# NEW_LINE.net
KiCad netlist of a schematic drawn in EAGLE
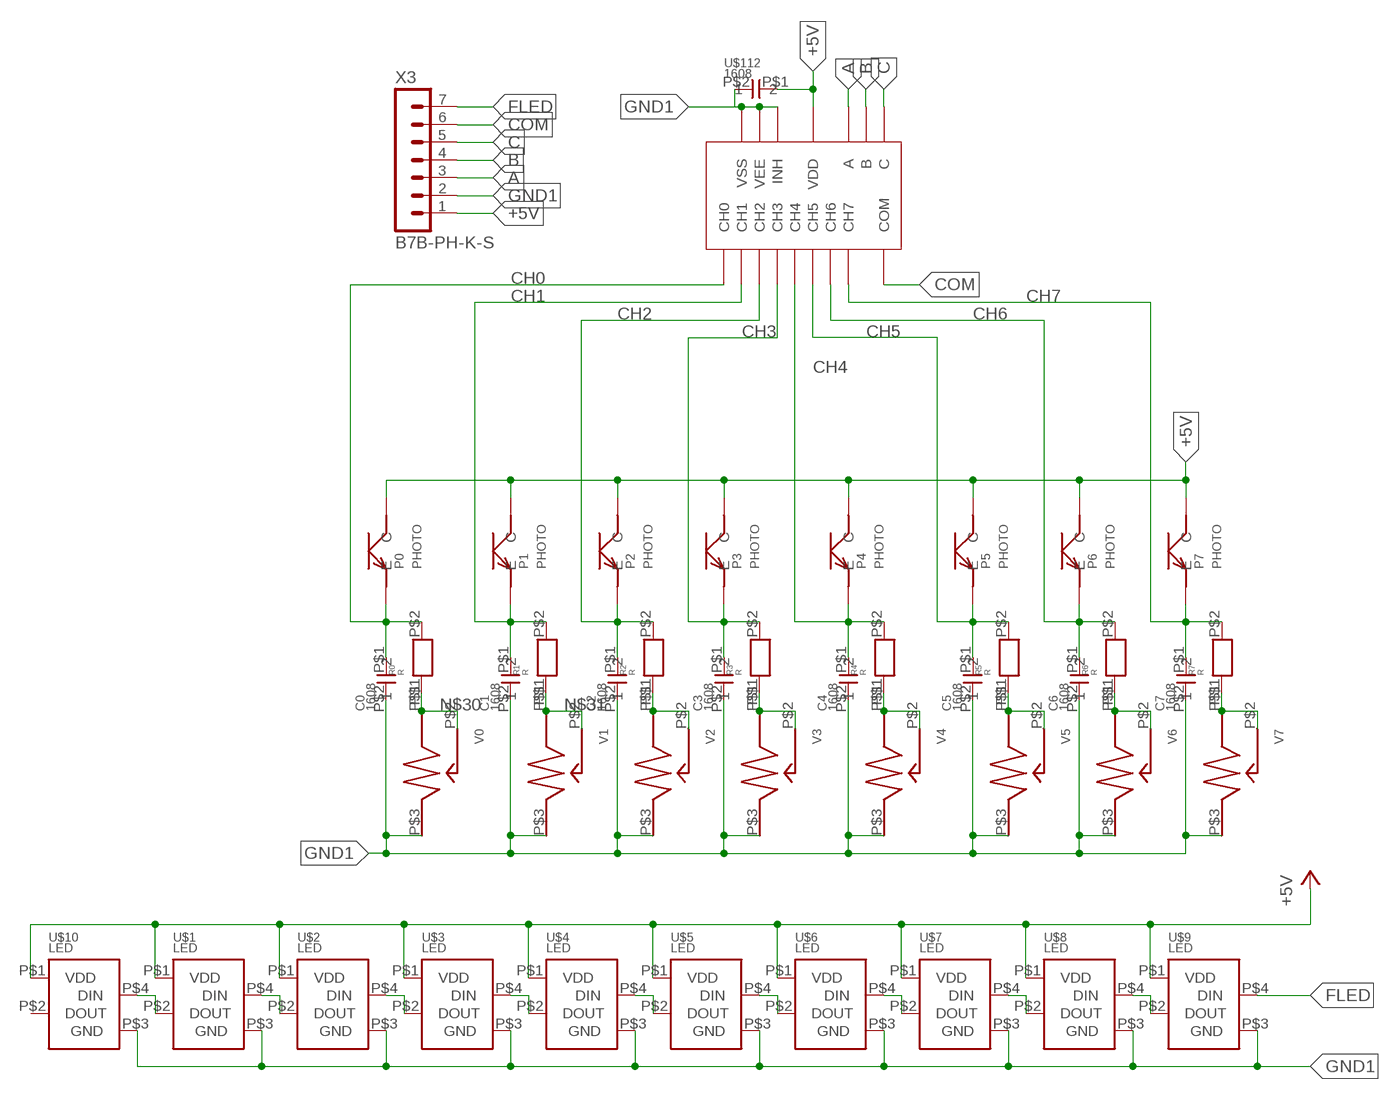
[diagram p0: schematic, sheet 2]

(export (version "E")
  (design (tool "Eeschema 10.0.6"))
  (components
    (comp (ref "C0")
      (value "1608")
      (footprint "eagle-import:CON")
      (libsource (lib "eagle-import") (part "1608"))
    )
    (comp (ref "C1")
      (value "1608")
      (footprint "eagle-import:CON")
      (libsource (lib "eagle-import") (part "1608"))
    )
    (comp (ref "C2")
      (value "1608")
      (footprint "eagle-import:CON")
      (libsource (lib "eagle-import") (part "1608"))
    )
    (comp (ref "C3")
      (value "1608")
      (footprint "eagle-import:CON")
      (libsource (lib "eagle-import") (part "1608"))
    )
    (comp (ref "C4")
      (value "1608")
      (footprint "eagle-import:CON")
      (libsource (lib "eagle-import") (part "1608"))
    )
    (comp (ref "C5")
      (value "1608")
      (footprint "eagle-import:CON")
      (libsource (lib "eagle-import") (part "1608"))
    )
    (comp (ref "C6")
      (value "1608")
      (footprint "eagle-import:CON")
      (libsource (lib "eagle-import") (part "1608"))
    )
    (comp (ref "C7")
      (value "1608")
      (footprint "eagle-import:CON")
      (libsource (lib "eagle-import") (part "1608"))
    )
    (comp (ref "P0")
      (value "PHOTO")
      (footprint "eagle-import:PHOTO")
      (libsource (lib "eagle-import") (part "PHOTO"))
    )
    (comp (ref "P1")
      (value "PHOTO")
      (footprint "eagle-import:PHOTO")
      (libsource (lib "eagle-import") (part "PHOTO"))
    )
    (comp (ref "P2")
      (value "PHOTO")
      (footprint "eagle-import:PHOTO")
      (libsource (lib "eagle-import") (part "PHOTO"))
    )
    (comp (ref "P3")
      (value "PHOTO")
      (footprint "eagle-import:PHOTO")
      (libsource (lib "eagle-import") (part "PHOTO"))
    )
    (comp (ref "P4")
      (value "PHOTO")
      (footprint "eagle-import:PHOTO")
      (libsource (lib "eagle-import") (part "PHOTO"))
    )
    (comp (ref "P5")
      (value "PHOTO")
      (footprint "eagle-import:PHOTO")
      (libsource (lib "eagle-import") (part "PHOTO"))
    )
    (comp (ref "P6")
      (value "PHOTO")
      (footprint "eagle-import:PHOTO")
      (libsource (lib "eagle-import") (part "PHOTO"))
    )
    (comp (ref "P7")
      (value "PHOTO")
      (footprint "eagle-import:PHOTO")
      (libsource (lib "eagle-import") (part "PHOTO"))
    )
    (comp (ref "R0") (value "R") (footprint "eagle-import:1608") (libsource (lib "eagle-import") (part "R")))
    (comp (ref "R1") (value "R") (footprint "eagle-import:1608") (libsource (lib "eagle-import") (part "R")))
    (comp (ref "R2") (value "R") (footprint "eagle-import:1608") (libsource (lib "eagle-import") (part "R")))
    (comp (ref "R3") (value "R") (footprint "eagle-import:1608") (libsource (lib "eagle-import") (part "R")))
    (comp (ref "R4") (value "R") (footprint "eagle-import:1608") (libsource (lib "eagle-import") (part "R")))
    (comp (ref "R5") (value "R") (footprint "eagle-import:1608") (libsource (lib "eagle-import") (part "R")))
    (comp (ref "R6") (value "R") (footprint "eagle-import:1608") (libsource (lib "eagle-import") (part "R")))
    (comp (ref "R7") (value "R") (footprint "eagle-import:1608") (libsource (lib "eagle-import") (part "R")))
    (comp (ref "U$1")
      (value "LED")
      (footprint "eagle-import:LED")
      (libsource (lib "eagle-import") (part "LED"))
    )
    (comp (ref "U$2")
      (value "LED")
      (footprint "eagle-import:LED")
      (libsource (lib "eagle-import") (part "LED"))
    )
    (comp (ref "U$3")
      (value "LED")
      (footprint "eagle-import:LED")
      (libsource (lib "eagle-import") (part "LED"))
    )
    (comp (ref "U$4")
      (value "LED")
      (footprint "eagle-import:LED")
      (libsource (lib "eagle-import") (part "LED"))
    )
    (comp (ref "U$5")
      (value "LED")
      (footprint "eagle-import:LED")
      (libsource (lib "eagle-import") (part "LED"))
    )
    (comp (ref "U$6")
      (value "LED")
      (footprint "eagle-import:LED")
      (libsource (lib "eagle-import") (part "LED"))
    )
    (comp (ref "U$7")
      (value "LED")
      (footprint "eagle-import:LED")
      (libsource (lib "eagle-import") (part "LED"))
    )
    (comp (ref "U$8")
      (value "LED")
      (footprint "eagle-import:LED")
      (libsource (lib "eagle-import") (part "LED"))
    )
    (comp (ref "U$9")
      (value "LED")
      (footprint "eagle-import:LED")
      (libsource (lib "eagle-import") (part "LED"))
    )
    (comp (ref "U$10")
      (value "LED")
      (footprint "eagle-import:LED")
      (libsource (lib "eagle-import") (part "LED"))
    )
    (comp (ref "U$79")
      (value "AM")
      (footprint "eagle-import:SOP65P640X120-16N")
      (libsource (lib "eagle-import") (part "AM"))
    )
    (comp (ref "U$112")
      (value "1608")
      (footprint "eagle-import:CON")
      (libsource (lib "eagle-import") (part "1608"))
    )
    (comp (ref "V0") (value "VR") (footprint "eagle-import:VR") (libsource (lib "eagle-import") (part "VR")))
    (comp (ref "V1") (value "VR") (footprint "eagle-import:VR") (libsource (lib "eagle-import") (part "VR")))
    (comp (ref "V2") (value "VR") (footprint "eagle-import:VR") (libsource (lib "eagle-import") (part "VR")))
    (comp (ref "V3") (value "VR") (footprint "eagle-import:VR") (libsource (lib "eagle-import") (part "VR")))
    (comp (ref "V4") (value "VR") (footprint "eagle-import:VR") (libsource (lib "eagle-import") (part "VR")))
    (comp (ref "V5") (value "VR") (footprint "eagle-import:VR") (libsource (lib "eagle-import") (part "VR")))
    (comp (ref "V6") (value "VR") (footprint "eagle-import:VR") (libsource (lib "eagle-import") (part "VR")))
    (comp (ref "V7") (value "VR") (footprint "eagle-import:VR") (libsource (lib "eagle-import") (part "VR")))
    (comp (ref "X3")
      (value "B7B-PH-K-S")
      (footprint "eagle-import:B7B-PH-K-S")
      (libsource (lib "eagle-import") (part "B7B-PH-K-S"))
    )
  )
  (nets
    (net (code "1") (name "+5V") (class "Default")
      (node (ref "P0") (pin "P$1") (pinfunction "C_P$1") (pintype "bidirectional"))
      (node (ref "P1") (pin "P$1") (pinfunction "C_P$1") (pintype "bidirectional"))
      (node (ref "P2") (pin "P$1") (pinfunction "C_P$1") (pintype "bidirectional"))
      (node (ref "P3") (pin "P$1") (pinfunction "C_P$1") (pintype "bidirectional"))
      (node (ref "P4") (pin "P$1") (pinfunction "C_P$1") (pintype "bidirectional"))
      (node (ref "P5") (pin "P$1") (pinfunction "C_P$1") (pintype "bidirectional"))
      (node (ref "P6") (pin "P$1") (pinfunction "C_P$1") (pintype "bidirectional"))
      (node (ref "P7") (pin "P$1") (pinfunction "C_P$1") (pintype "bidirectional"))
      (node (ref "U$1") (pin "P$1") (pinfunction "VDD_P$1") (pintype "bidirectional"))
      (node (ref "U$10") (pin "P$1") (pinfunction "VDD_P$1") (pintype "bidirectional"))
      (node (ref "U$112") (pin "P$1") (pinfunction "1_P$1") (pintype "bidirectional"))
      (node (ref "U$2") (pin "P$1") (pinfunction "VDD_P$1") (pintype "bidirectional"))
      (node (ref "U$3") (pin "P$1") (pinfunction "VDD_P$1") (pintype "bidirectional"))
      (node (ref "U$4") (pin "P$1") (pinfunction "VDD_P$1") (pintype "bidirectional"))
      (node (ref "U$5") (pin "P$1") (pinfunction "VDD_P$1") (pintype "bidirectional"))
      (node (ref "U$6") (pin "P$1") (pinfunction "VDD_P$1") (pintype "bidirectional"))
      (node (ref "U$7") (pin "P$1") (pinfunction "VDD_P$1") (pintype "bidirectional"))
      (node (ref "U$79") (pin "16") (pinfunction "VDD_16") (pintype "bidirectional"))
      (node (ref "U$8") (pin "P$1") (pinfunction "VDD_P$1") (pintype "bidirectional"))
      (node (ref "U$9") (pin "P$1") (pinfunction "VDD_P$1") (pintype "bidirectional"))
      (node (ref "X3") (pin "1") (pinfunction "1_1") (pintype "passive"))
    )
    (net (code "2") (name "A") (class "Default")
      (node (ref "U$79") (pin "11") (pinfunction "A_11") (pintype "bidirectional"))
      (node (ref "X3") (pin "3") (pinfunction "3_3") (pintype "passive"))
    )
    (net (code "3") (name "B") (class "Default")
      (node (ref "U$79") (pin "10") (pinfunction "B_10") (pintype "bidirectional"))
      (node (ref "X3") (pin "4") (pinfunction "4_4") (pintype "passive"))
    )
    (net (code "4") (name "C") (class "Default")
      (node (ref "U$79") (pin "9") (pinfunction "C_9") (pintype "bidirectional"))
      (node (ref "X3") (pin "5") (pinfunction "5_5") (pintype "passive"))
    )
    (net (code "5") (name "CH0") (class "Default")
      (node (ref "C0") (pin "P$1") (pinfunction "1_P$1") (pintype "bidirectional"))
      (node (ref "P0") (pin "P$2") (pinfunction "E_P$2") (pintype "bidirectional"))
      (node (ref "R0") (pin "P$2") (pinfunction "P$2_P$2") (pintype "bidirectional"))
      (node (ref "U$79") (pin "13") (pinfunction "CH0_13") (pintype "bidirectional"))
    )
    (net (code "6") (name "CH1") (class "Default")
      (node (ref "C1") (pin "P$1") (pinfunction "1_P$1") (pintype "bidirectional"))
      (node (ref "P1") (pin "P$2") (pinfunction "E_P$2") (pintype "bidirectional"))
      (node (ref "R1") (pin "P$2") (pinfunction "P$2_P$2") (pintype "bidirectional"))
      (node (ref "U$79") (pin "14") (pinfunction "CH1_14") (pintype "bidirectional"))
    )
    (net (code "7") (name "CH2") (class "Default")
      (node (ref "C2") (pin "P$1") (pinfunction "1_P$1") (pintype "bidirectional"))
      (node (ref "P2") (pin "P$2") (pinfunction "E_P$2") (pintype "bidirectional"))
      (node (ref "R2") (pin "P$2") (pinfunction "P$2_P$2") (pintype "bidirectional"))
      (node (ref "U$79") (pin "15") (pinfunction "CH2_15") (pintype "bidirectional"))
    )
    (net (code "8") (name "CH3") (class "Default")
      (node (ref "C3") (pin "P$1") (pinfunction "1_P$1") (pintype "bidirectional"))
      (node (ref "P3") (pin "P$2") (pinfunction "E_P$2") (pintype "bidirectional"))
      (node (ref "R3") (pin "P$2") (pinfunction "P$2_P$2") (pintype "bidirectional"))
      (node (ref "U$79") (pin "12") (pinfunction "CH3_12") (pintype "bidirectional"))
    )
    (net (code "9") (name "CH4") (class "Default")
      (node (ref "C4") (pin "P$1") (pinfunction "1_P$1") (pintype "bidirectional"))
      (node (ref "P4") (pin "P$2") (pinfunction "E_P$2") (pintype "bidirectional"))
      (node (ref "R4") (pin "P$2") (pinfunction "P$2_P$2") (pintype "bidirectional"))
      (node (ref "U$79") (pin "1") (pinfunction "CH4_1") (pintype "bidirectional"))
    )
    (net (code "10") (name "CH5") (class "Default")
      (node (ref "C5") (pin "P$1") (pinfunction "1_P$1") (pintype "bidirectional"))
      (node (ref "P5") (pin "P$2") (pinfunction "E_P$2") (pintype "bidirectional"))
      (node (ref "R5") (pin "P$2") (pinfunction "P$2_P$2") (pintype "bidirectional"))
      (node (ref "U$79") (pin "5") (pinfunction "CH5_5") (pintype "bidirectional"))
    )
    (net (code "11") (name "CH6") (class "Default")
      (node (ref "C6") (pin "P$1") (pinfunction "1_P$1") (pintype "bidirectional"))
      (node (ref "P6") (pin "P$2") (pinfunction "E_P$2") (pintype "bidirectional"))
      (node (ref "R6") (pin "P$2") (pinfunction "P$2_P$2") (pintype "bidirectional"))
      (node (ref "U$79") (pin "2") (pinfunction "CH6_2") (pintype "bidirectional"))
    )
    (net (code "12") (name "CH7") (class "Default")
      (node (ref "C7") (pin "P$1") (pinfunction "1_P$1") (pintype "bidirectional"))
      (node (ref "P7") (pin "P$2") (pinfunction "E_P$2") (pintype "bidirectional"))
      (node (ref "R7") (pin "P$2") (pinfunction "P$2_P$2") (pintype "bidirectional"))
      (node (ref "U$79") (pin "4") (pinfunction "CH7_4") (pintype "bidirectional"))
    )
    (net (code "13") (name "COM") (class "Default")
      (node (ref "U$79") (pin "3") (pinfunction "COM_3") (pintype "bidirectional"))
      (node (ref "X3") (pin "6") (pinfunction "6_6") (pintype "passive"))
    )
    (net (code "14") (name "FLED") (class "Default")
      (node (ref "U$9") (pin "P$4") (pinfunction "DIN_P$4") (pintype "bidirectional"))
      (node (ref "X3") (pin "7") (pinfunction "7_7") (pintype "passive"))
    )
    (net (code "15") (name "GND1") (class "Default")
      (node (ref "C0") (pin "P$2") (pinfunction "2_P$2") (pintype "bidirectional"))
      (node (ref "C1") (pin "P$2") (pinfunction "2_P$2") (pintype "bidirectional"))
      (node (ref "C2") (pin "P$2") (pinfunction "2_P$2") (pintype "bidirectional"))
      (node (ref "C3") (pin "P$2") (pinfunction "2_P$2") (pintype "bidirectional"))
      (node (ref "C4") (pin "P$2") (pinfunction "2_P$2") (pintype "bidirectional"))
      (node (ref "C5") (pin "P$2") (pinfunction "2_P$2") (pintype "bidirectional"))
      (node (ref "C6") (pin "P$2") (pinfunction "2_P$2") (pintype "bidirectional"))
      (node (ref "C7") (pin "P$2") (pinfunction "2_P$2") (pintype "bidirectional"))
      (node (ref "U$1") (pin "P$3") (pinfunction "GND_P$3") (pintype "bidirectional"))
      (node (ref "U$10") (pin "P$3") (pinfunction "GND_P$3") (pintype "bidirectional"))
      (node (ref "U$112") (pin "P$2") (pinfunction "2_P$2") (pintype "bidirectional"))
      (node (ref "U$2") (pin "P$3") (pinfunction "GND_P$3") (pintype "bidirectional"))
      (node (ref "U$3") (pin "P$3") (pinfunction "GND_P$3") (pintype "bidirectional"))
      (node (ref "U$4") (pin "P$3") (pinfunction "GND_P$3") (pintype "bidirectional"))
      (node (ref "U$5") (pin "P$3") (pinfunction "GND_P$3") (pintype "bidirectional"))
      (node (ref "U$6") (pin "P$3") (pinfunction "GND_P$3") (pintype "bidirectional"))
      (node (ref "U$7") (pin "P$3") (pinfunction "GND_P$3") (pintype "bidirectional"))
      (node (ref "U$79") (pin "6") (pinfunction "INH_6") (pintype "bidirectional"))
      (node (ref "U$79") (pin "7") (pinfunction "VEE_7") (pintype "bidirectional"))
      (node (ref "U$79") (pin "8") (pinfunction "VSS_8") (pintype "bidirectional"))
      (node (ref "U$8") (pin "P$3") (pinfunction "GND_P$3") (pintype "bidirectional"))
      (node (ref "U$9") (pin "P$3") (pinfunction "GND_P$3") (pintype "bidirectional"))
      (node (ref "V0") (pin "P$3") (pinfunction "P$3_P$3") (pintype "bidirectional"))
      (node (ref "V1") (pin "P$3") (pinfunction "P$3_P$3") (pintype "bidirectional"))
      (node (ref "V2") (pin "P$3") (pinfunction "P$3_P$3") (pintype "bidirectional"))
      (node (ref "V3") (pin "P$3") (pinfunction "P$3_P$3") (pintype "bidirectional"))
      (node (ref "V4") (pin "P$3") (pinfunction "P$3_P$3") (pintype "bidirectional"))
      (node (ref "V5") (pin "P$3") (pinfunction "P$3_P$3") (pintype "bidirectional"))
      (node (ref "V6") (pin "P$3") (pinfunction "P$3_P$3") (pintype "bidirectional"))
      (node (ref "V7") (pin "P$3") (pinfunction "P$3_P$3") (pintype "bidirectional"))
      (node (ref "X3") (pin "2") (pinfunction "2_2") (pintype "passive"))
    )
    (net (code "16") (name "N$30") (class "Default")
      (node (ref "R0") (pin "P$1") (pinfunction "P$1_P$1") (pintype "bidirectional"))
      (node (ref "V0") (pin "P$1") (pinfunction "P$1_P$1") (pintype "bidirectional"))
      (node (ref "V0") (pin "P$2") (pinfunction "P$2_P$2") (pintype "bidirectional"))
    )
    (net (code "17") (name "N$31") (class "Default")
      (node (ref "R1") (pin "P$1") (pinfunction "P$1_P$1") (pintype "bidirectional"))
      (node (ref "V1") (pin "P$1") (pinfunction "P$1_P$1") (pintype "bidirectional"))
      (node (ref "V1") (pin "P$2") (pinfunction "P$2_P$2") (pintype "bidirectional"))
    )
    (net (code "18") (name "Net-(R2-PadP$1)") (class "Default")
      (node (ref "R2") (pin "P$1") (pinfunction "P$1_P$1") (pintype "bidirectional"))
      (node (ref "V2") (pin "P$1") (pinfunction "P$1_P$1") (pintype "bidirectional"))
      (node (ref "V2") (pin "P$2") (pinfunction "P$2_P$2") (pintype "bidirectional"))
    )
    (net (code "19") (name "Net-(R3-PadP$1)") (class "Default")
      (node (ref "R3") (pin "P$1") (pinfunction "P$1_P$1") (pintype "bidirectional"))
      (node (ref "V3") (pin "P$1") (pinfunction "P$1_P$1") (pintype "bidirectional"))
      (node (ref "V3") (pin "P$2") (pinfunction "P$2_P$2") (pintype "bidirectional"))
    )
    (net (code "20") (name "Net-(R4-PadP$1)") (class "Default")
      (node (ref "R4") (pin "P$1") (pinfunction "P$1_P$1") (pintype "bidirectional"))
      (node (ref "V4") (pin "P$1") (pinfunction "P$1_P$1") (pintype "bidirectional"))
      (node (ref "V4") (pin "P$2") (pinfunction "P$2_P$2") (pintype "bidirectional"))
    )
    (net (code "21") (name "Net-(R5-PadP$1)") (class "Default")
      (node (ref "R5") (pin "P$1") (pinfunction "P$1_P$1") (pintype "bidirectional"))
      (node (ref "V5") (pin "P$1") (pinfunction "P$1_P$1") (pintype "bidirectional"))
      (node (ref "V5") (pin "P$2") (pinfunction "P$2_P$2") (pintype "bidirectional"))
    )
    (net (code "22") (name "Net-(R6-PadP$1)") (class "Default")
      (node (ref "R6") (pin "P$1") (pinfunction "P$1_P$1") (pintype "bidirectional"))
      (node (ref "V6") (pin "P$1") (pinfunction "P$1_P$1") (pintype "bidirectional"))
      (node (ref "V6") (pin "P$2") (pinfunction "P$2_P$2") (pintype "bidirectional"))
    )
    (net (code "23") (name "Net-(R7-PadP$1)") (class "Default")
      (node (ref "R7") (pin "P$1") (pinfunction "P$1_P$1") (pintype "bidirectional"))
      (node (ref "V7") (pin "P$1") (pinfunction "P$1_P$1") (pintype "bidirectional"))
      (node (ref "V7") (pin "P$2") (pinfunction "P$2_P$2") (pintype "bidirectional"))
    )
    (net (code "24") (name "Net-(U$1-DIN)") (class "Default")
      (node (ref "U$1") (pin "P$4") (pinfunction "DIN_P$4") (pintype "bidirectional"))
      (node (ref "U$2") (pin "P$2") (pinfunction "DOUT_P$2") (pintype "bidirectional"))
    )
    (net (code "25") (name "Net-(U$1-DOUT)") (class "Default")
      (node (ref "U$1") (pin "P$2") (pinfunction "DOUT_P$2") (pintype "bidirectional"))
      (node (ref "U$10") (pin "P$4") (pinfunction "DIN_P$4") (pintype "bidirectional"))
    )
    (net (code "26") (name "Net-(U$2-DIN)") (class "Default")
      (node (ref "U$2") (pin "P$4") (pinfunction "DIN_P$4") (pintype "bidirectional"))
      (node (ref "U$3") (pin "P$2") (pinfunction "DOUT_P$2") (pintype "bidirectional"))
    )
    (net (code "27") (name "Net-(U$3-DIN)") (class "Default")
      (node (ref "U$3") (pin "P$4") (pinfunction "DIN_P$4") (pintype "bidirectional"))
      (node (ref "U$4") (pin "P$2") (pinfunction "DOUT_P$2") (pintype "bidirectional"))
    )
    (net (code "28") (name "Net-(U$4-DIN)") (class "Default")
      (node (ref "U$4") (pin "P$4") (pinfunction "DIN_P$4") (pintype "bidirectional"))
      (node (ref "U$5") (pin "P$2") (pinfunction "DOUT_P$2") (pintype "bidirectional"))
    )
    (net (code "29") (name "Net-(U$5-DIN)") (class "Default")
      (node (ref "U$5") (pin "P$4") (pinfunction "DIN_P$4") (pintype "bidirectional"))
      (node (ref "U$6") (pin "P$2") (pinfunction "DOUT_P$2") (pintype "bidirectional"))
    )
    (net (code "30") (name "Net-(U$6-DIN)") (class "Default")
      (node (ref "U$6") (pin "P$4") (pinfunction "DIN_P$4") (pintype "bidirectional"))
      (node (ref "U$7") (pin "P$2") (pinfunction "DOUT_P$2") (pintype "bidirectional"))
    )
    (net (code "31") (name "Net-(U$7-DIN)") (class "Default")
      (node (ref "U$7") (pin "P$4") (pinfunction "DIN_P$4") (pintype "bidirectional"))
      (node (ref "U$8") (pin "P$2") (pinfunction "DOUT_P$2") (pintype "bidirectional"))
    )
    (net (code "32") (name "Net-(U$8-DIN)") (class "Default")
      (node (ref "U$8") (pin "P$4") (pinfunction "DIN_P$4") (pintype "bidirectional"))
      (node (ref "U$9") (pin "P$2") (pinfunction "DOUT_P$2") (pintype "bidirectional"))
    )
    (net (code "33") (name "unconnected-(U$10-DOUT-PadP$2)") (class "Default")
      (node (ref "U$10") (pin "P$2") (pinfunction "DOUT_P$2") (pintype "bidirectional"))
    )
  )
)
